# timetracker-1-3.net
KiCad netlist of a schematic drawn in EAGLE
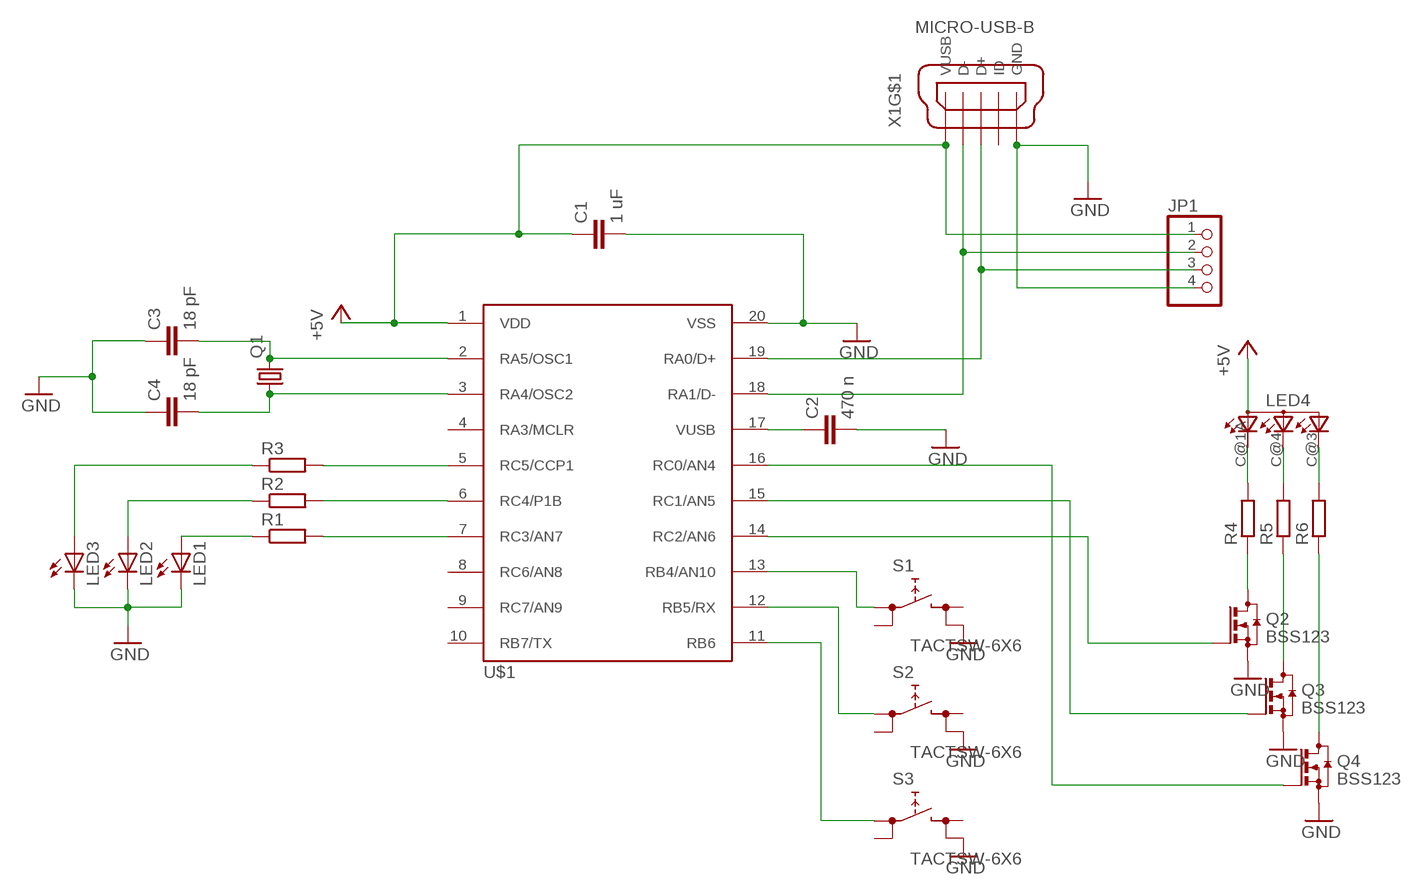
[diagram p0: schematic, sheet 1]

(export (version "E")
  (design (tool "Eeschema 10.0.6"))
  (components
    (comp (ref "C1")
      (value "1 uF")
      (footprint "eagle-import:C0805")
      (libsource (lib "eagle-import") (part "C-EUC0805"))
    )
    (comp (ref "C2")
      (value "470 n")
      (footprint "eagle-import:C0805")
      (libsource (lib "eagle-import") (part "C-EUC0805"))
    )
    (comp (ref "C3")
      (value "18 pF")
      (footprint "eagle-import:C0805")
      (libsource (lib "eagle-import") (part "C-EUC0805"))
    )
    (comp (ref "C4")
      (value "18 pF")
      (footprint "eagle-import:C0805")
      (libsource (lib "eagle-import") (part "C-EUC0805"))
    )
    (comp (ref "JP1")
      (value "PINHD-1X4")
      (footprint "eagle-import:1X04")
      (libsource (lib "eagle-import") (part "PINHD-1X4"))
    )
    (comp (ref "LED1")
      (value "LEDSML0805")
      (footprint "eagle-import:SML0805")
      (libsource (lib "eagle-import") (part "LEDSML0805"))
    )
    (comp (ref "LED2")
      (value "LEDSML0805")
      (footprint "eagle-import:SML0805")
      (libsource (lib "eagle-import") (part "LEDSML0805"))
    )
    (comp (ref "LED3")
      (value "LEDSML0805")
      (footprint "eagle-import:SML0805")
      (libsource (lib "eagle-import") (part "LEDSML0805"))
    )
    (comp (ref "LED4")
      (value "RGBLED-3P-LCC-4")
      (footprint "eagle-import:P-LCC-4")
      (libsource (lib "eagle-import") (part "RGBLED-3P-LCC-4"))
    )
    (comp (ref "Q1")
      (value "CRYSTALHC49UP")
      (footprint "eagle-import:HC49UP")
      (libsource (lib "eagle-import") (part "CRYSTALHC49UP"))
    )
    (comp (ref "Q2")
      (value "BSS123")
      (footprint "eagle-import:SOT23")
      (libsource (lib "eagle-import") (part "BSS123"))
    )
    (comp (ref "Q3")
      (value "BSS123")
      (footprint "eagle-import:SOT23")
      (libsource (lib "eagle-import") (part "BSS123"))
    )
    (comp (ref "Q4")
      (value "BSS123")
      (footprint "eagle-import:SOT23")
      (libsource (lib "eagle-import") (part "BSS123"))
    )
    (comp (ref "R1")
      (value "R-EU_R0805")
      (footprint "eagle-import:R0805")
      (libsource (lib "eagle-import") (part "R-EU_R0805"))
    )
    (comp (ref "R2")
      (value "R-EU_R0805")
      (footprint "eagle-import:R0805")
      (libsource (lib "eagle-import") (part "R-EU_R0805"))
    )
    (comp (ref "R3")
      (value "R-EU_R0805")
      (footprint "eagle-import:R0805")
      (libsource (lib "eagle-import") (part "R-EU_R0805"))
    )
    (comp (ref "R4")
      (value "R-EU_R0805")
      (footprint "eagle-import:R0805")
      (libsource (lib "eagle-import") (part "R-EU_R0805"))
    )
    (comp (ref "R5")
      (value "R-EU_R0805")
      (footprint "eagle-import:R0805")
      (libsource (lib "eagle-import") (part "R-EU_R0805"))
    )
    (comp (ref "R6")
      (value "R-EU_R0805")
      (footprint "eagle-import:R0805")
      (libsource (lib "eagle-import") (part "R-EU_R0805"))
    )
    (comp (ref "S1")
      (value "TACTSW-6X6")
      (footprint "eagle-import:TACTSW-6X6")
      (libsource (lib "eagle-import") (part "TACTSW-6X6"))
    )
    (comp (ref "S2")
      (value "TACTSW-6X6")
      (footprint "eagle-import:TACTSW-6X6")
      (libsource (lib "eagle-import") (part "TACTSW-6X6"))
    )
    (comp (ref "S3")
      (value "TACTSW-6X6")
      (footprint "eagle-import:TACTSW-6X6")
      (libsource (lib "eagle-import") (part "TACTSW-6X6"))
    )
    (comp (ref "U$1")
      (value "PIC18F14K50SMD")
      (footprint "eagle-import:DIL20-SMD")
      (libsource (lib "eagle-import") (part "PIC18F14K50SMD"))
    )
    (comp (ref "X1")
      (value "MICRO-USB-B")
      (footprint "eagle-import:MICRO-B-PAC")
      (libsource (lib "eagle-import") (part "MICRO-USB-B"))
    )
  )
  (nets
    (net (code "1") (name "+5V") (class "Default")
      (node (ref "C1") (pin "1") (pinfunction "1_1") (pintype "passive"))
      (node (ref "JP1") (pin "1") (pinfunction "1_1") (pintype "passive"))
      (node (ref "LED4") (pin "A") (pinfunction "A2_A") (pintype "passive"))
      (node (ref "U$1") (pin "1") (pinfunction "VDD_1") (pintype "bidirectional"))
      (node (ref "X1") (pin "1") (pinfunction "VUSB_1") (pintype "passive"))
    )
    (net (code "2") (name "GND") (class "Default")
      (node (ref "C1") (pin "2") (pinfunction "2_2") (pintype "passive"))
      (node (ref "C2") (pin "2") (pinfunction "2_2") (pintype "passive"))
      (node (ref "C3") (pin "1") (pinfunction "1_1") (pintype "passive"))
      (node (ref "C4") (pin "1") (pinfunction "1_1") (pintype "passive"))
      (node (ref "JP1") (pin "4") (pinfunction "4_4") (pintype "passive"))
      (node (ref "LED1") (pin "C") (pinfunction "C_C") (pintype "passive"))
      (node (ref "LED2") (pin "C") (pinfunction "C_C") (pintype "passive"))
      (node (ref "LED3") (pin "C") (pinfunction "C_C") (pintype "passive"))
      (node (ref "Q2") (pin "2") (pinfunction "S_2") (pintype "passive"))
      (node (ref "Q3") (pin "2") (pinfunction "S_2") (pintype "passive"))
      (node (ref "Q4") (pin "2") (pinfunction "S_2") (pintype "passive"))
      (node (ref "S1") (pin "4") (pinfunction "2.2_4") (pintype "passive"))
      (node (ref "S2") (pin "4") (pinfunction "2.2_4") (pintype "passive"))
      (node (ref "S3") (pin "4") (pinfunction "2.2_4") (pintype "passive"))
      (node (ref "U$1") (pin "20") (pinfunction "VSS_20") (pintype "bidirectional"))
      (node (ref "X1") (pin "5") (pinfunction "GND_5") (pintype "passive"))
    )
    (net (code "3") (name "Net-(LED1-PadA)") (class "Default")
      (node (ref "LED1") (pin "A") (pinfunction "A_A") (pintype "passive"))
      (node (ref "R1") (pin "1") (pinfunction "1_1") (pintype "passive"))
    )
    (net (code "4") (name "Net-(LED2-PadA)") (class "Default")
      (node (ref "LED2") (pin "A") (pinfunction "A_A") (pintype "passive"))
      (node (ref "R2") (pin "1") (pinfunction "1_1") (pintype "passive"))
    )
    (net (code "5") (name "Net-(LED3-PadA)") (class "Default")
      (node (ref "LED3") (pin "A") (pinfunction "A_A") (pintype "passive"))
      (node (ref "R3") (pin "1") (pinfunction "1_1") (pintype "passive"))
    )
    (net (code "6") (name "Net-(LED4-CBLUE)") (class "Default")
      (node (ref "LED4") (pin "C@3") (pinfunction "CBLUE_C@3") (pintype "passive"))
      (node (ref "R6") (pin "2") (pinfunction "2_2") (pintype "passive"))
    )
    (net (code "7") (name "Net-(LED4-CGREEN)") (class "Default")
      (node (ref "LED4") (pin "C@4") (pinfunction "CGREEN_C@4") (pintype "passive"))
      (node (ref "R5") (pin "2") (pinfunction "2_2") (pintype "passive"))
    )
    (net (code "8") (name "Net-(LED4-CRED)") (class "Default")
      (node (ref "LED4") (pin "C@1") (pinfunction "CRED_C@1") (pintype "passive"))
      (node (ref "R4") (pin "2") (pinfunction "2_2") (pintype "passive"))
    )
    (net (code "9") (name "Net-(Q2-D)") (class "Default")
      (node (ref "Q2") (pin "3") (pinfunction "D_3") (pintype "passive"))
      (node (ref "R4") (pin "1") (pinfunction "1_1") (pintype "passive"))
    )
    (net (code "10") (name "Net-(Q2-G)") (class "Default")
      (node (ref "Q2") (pin "1") (pinfunction "G_1") (pintype "passive"))
      (node (ref "U$1") (pin "14") (pinfunction "RC2/AN6_14") (pintype "bidirectional"))
    )
    (net (code "11") (name "Net-(Q3-D)") (class "Default")
      (node (ref "Q3") (pin "3") (pinfunction "D_3") (pintype "passive"))
      (node (ref "R5") (pin "1") (pinfunction "1_1") (pintype "passive"))
    )
    (net (code "12") (name "Net-(Q3-G)") (class "Default")
      (node (ref "Q3") (pin "1") (pinfunction "G_1") (pintype "passive"))
      (node (ref "U$1") (pin "15") (pinfunction "RC1/AN5_15") (pintype "bidirectional"))
    )
    (net (code "13") (name "Net-(Q4-D)") (class "Default")
      (node (ref "Q4") (pin "3") (pinfunction "D_3") (pintype "passive"))
      (node (ref "R6") (pin "1") (pinfunction "1_1") (pintype "passive"))
    )
    (net (code "14") (name "Net-(Q4-G)") (class "Default")
      (node (ref "Q4") (pin "1") (pinfunction "G_1") (pintype "passive"))
      (node (ref "U$1") (pin "16") (pinfunction "RC0/AN4_16") (pintype "bidirectional"))
    )
    (net (code "15") (name "Net-(S1-1.1)") (class "Default")
      (node (ref "S1") (pin "1") (pinfunction "1.1_1") (pintype "passive"))
      (node (ref "U$1") (pin "13") (pinfunction "RB4/AN10_13") (pintype "bidirectional"))
    )
    (net (code "16") (name "Net-(S2-1.1)") (class "Default")
      (node (ref "S2") (pin "1") (pinfunction "1.1_1") (pintype "passive"))
      (node (ref "U$1") (pin "12") (pinfunction "RB5/RX_12") (pintype "bidirectional"))
    )
    (net (code "17") (name "Net-(S3-1.1)") (class "Default")
      (node (ref "S3") (pin "1") (pinfunction "1.1_1") (pintype "passive"))
      (node (ref "U$1") (pin "11") (pinfunction "RB6_11") (pintype "bidirectional"))
    )
    (net (code "18") (name "Net-(U$1-RA0{slash}D+)") (class "Default")
      (node (ref "JP1") (pin "3") (pinfunction "3_3") (pintype "passive"))
      (node (ref "U$1") (pin "19") (pinfunction "RA0/D+_19") (pintype "bidirectional"))
      (node (ref "X1") (pin "3") (pinfunction "D+_3") (pintype "passive"))
    )
    (net (code "19") (name "Net-(U$1-RA1{slash}D-)") (class "Default")
      (node (ref "JP1") (pin "2") (pinfunction "2_2") (pintype "passive"))
      (node (ref "U$1") (pin "18") (pinfunction "RA1/D-_18") (pintype "bidirectional"))
      (node (ref "X1") (pin "2") (pinfunction "D-_2") (pintype "passive"))
    )
    (net (code "20") (name "Net-(U$1-RA4{slash}OSC2)") (class "Default")
      (node (ref "C4") (pin "2") (pinfunction "2_2") (pintype "passive"))
      (node (ref "Q1") (pin "1") (pinfunction "1_1") (pintype "passive"))
      (node (ref "U$1") (pin "3") (pinfunction "RA4/OSC2_3") (pintype "bidirectional"))
    )
    (net (code "21") (name "Net-(U$1-RA5{slash}OSC1)") (class "Default")
      (node (ref "C3") (pin "2") (pinfunction "2_2") (pintype "passive"))
      (node (ref "Q1") (pin "2") (pinfunction "2_2") (pintype "passive"))
      (node (ref "U$1") (pin "2") (pinfunction "RA5/OSC1_2") (pintype "bidirectional"))
    )
    (net (code "22") (name "Net-(U$1-RC3{slash}AN7)") (class "Default")
      (node (ref "R1") (pin "2") (pinfunction "2_2") (pintype "passive"))
      (node (ref "U$1") (pin "7") (pinfunction "RC3/AN7_7") (pintype "bidirectional"))
    )
    (net (code "23") (name "Net-(U$1-RC4{slash}P1B)") (class "Default")
      (node (ref "R2") (pin "2") (pinfunction "2_2") (pintype "passive"))
      (node (ref "U$1") (pin "6") (pinfunction "RC4/P1B_6") (pintype "bidirectional"))
    )
    (net (code "24") (name "Net-(U$1-RC5{slash}CCP1)") (class "Default")
      (node (ref "R3") (pin "2") (pinfunction "2_2") (pintype "passive"))
      (node (ref "U$1") (pin "5") (pinfunction "RC5/CCP1_5") (pintype "bidirectional"))
    )
    (net (code "25") (name "Net-(U$1-VUSB)") (class "Default")
      (node (ref "C2") (pin "1") (pinfunction "1_1") (pintype "passive"))
      (node (ref "U$1") (pin "17") (pinfunction "VUSB_17") (pintype "bidirectional"))
    )
    (net (code "26") (name "unconnected-(S1-1.2-Pad2)") (class "Default")
      (node (ref "S1") (pin "2") (pinfunction "1.2_2") (pintype "passive"))
    )
    (net (code "27") (name "unconnected-(S1-2.1-Pad3)") (class "Default")
      (node (ref "S1") (pin "3") (pinfunction "2.1_3") (pintype "passive"))
    )
    (net (code "28") (name "unconnected-(S2-1.2-Pad2)") (class "Default")
      (node (ref "S2") (pin "2") (pinfunction "1.2_2") (pintype "passive"))
    )
    (net (code "29") (name "unconnected-(S2-2.1-Pad3)") (class "Default")
      (node (ref "S2") (pin "3") (pinfunction "2.1_3") (pintype "passive"))
    )
    (net (code "30") (name "unconnected-(S3-1.2-Pad2)") (class "Default")
      (node (ref "S3") (pin "2") (pinfunction "1.2_2") (pintype "passive"))
    )
    (net (code "31") (name "unconnected-(S3-2.1-Pad3)") (class "Default")
      (node (ref "S3") (pin "3") (pinfunction "2.1_3") (pintype "passive"))
    )
    (net (code "32") (name "unconnected-(U$1-RA3{slash}MCLR-Pad4)") (class "Default")
      (node (ref "U$1") (pin "4") (pinfunction "RA3/MCLR_4") (pintype "bidirectional"))
    )
    (net (code "33") (name "unconnected-(U$1-RB7{slash}TX-Pad10)") (class "Default")
      (node (ref "U$1") (pin "10") (pinfunction "RB7/TX_10") (pintype "bidirectional"))
    )
    (net (code "34") (name "unconnected-(U$1-RC6{slash}AN8-Pad8)") (class "Default")
      (node (ref "U$1") (pin "8") (pinfunction "RC6/AN8_8") (pintype "bidirectional"))
    )
    (net (code "35") (name "unconnected-(U$1-RC7{slash}AN9-Pad9)") (class "Default")
      (node (ref "U$1") (pin "9") (pinfunction "RC7/AN9_9") (pintype "bidirectional"))
    )
    (net (code "36") (name "unconnected-(X1A-ID-Pad4)") (class "Default")
      (node (ref "X1") (pin "4") (pinfunction "ID_4") (pintype "passive"))
    )
  )
)
